# LED_Example_v24_1_2.net
KiCad netlist of a schematic drawn in Altium Designer
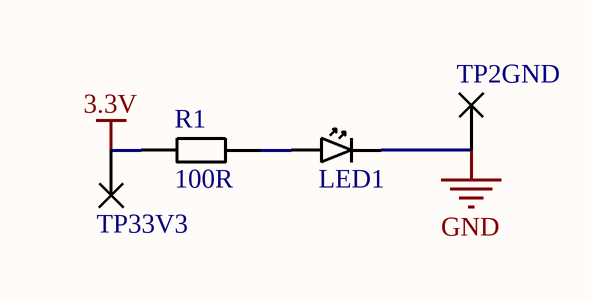
[diagram p0: LED_Example_v24.1.2.SchDoc]

(export (version "E")
  (design (tool "Eeschema 10.0.6"))
  (components
    (comp (ref "LED1")
      (value "LED (0603) orange AEC-Q101")
      (footprint "0603 (LED)")
      (description "LED orange 20mA AEC-Q101")
      (libsource (lib "LED_TH_VAR_FER") (part "LED (0603) orange AEC-Q101"))
    )
    (comp (ref "R1")
      (value "100R")
      (footprint "R0402")
      (description "1% 0402 0.063W 100ppm")
      (fields (field (name "Comment") "100R (0402)"))
      (libsource (lib "Res") (part "100R (0402)"))
    )
    (comp (ref "TP2") (value "GND") (libsource (lib "Wirepad") (part "Pad")))
    (comp (ref "TP3") (value "3V3") (libsource (lib "Wirepad") (part "Pad")))
  )
  (nets
    (net (code "1") (name "3.3V") (class "Default")
      (node (ref "R1") (pin "1") (pinfunction "1_1") (pintype "passive"))
      (node (ref "TP3") (pin "1") (pinfunction "1_1") (pintype "passive"))
    )
    (net (code "2") (name "GND") (class "Default")
      (node (ref "LED1") (pin "K") (pinfunction "2_K") (pintype "passive"))
      (node (ref "TP2") (pin "1") (pinfunction "1_1") (pintype "passive"))
    )
    (net (code "3") (name "Net-(LED1-1)") (class "Default")
      (node (ref "LED1") (pin "A") (pinfunction "1_A") (pintype "passive"))
      (node (ref "R1") (pin "2") (pinfunction "2_2") (pintype "passive"))
    )
  )
)
